# smartStarter.net
KiCad netlist of a schematic drawn in EAGLE
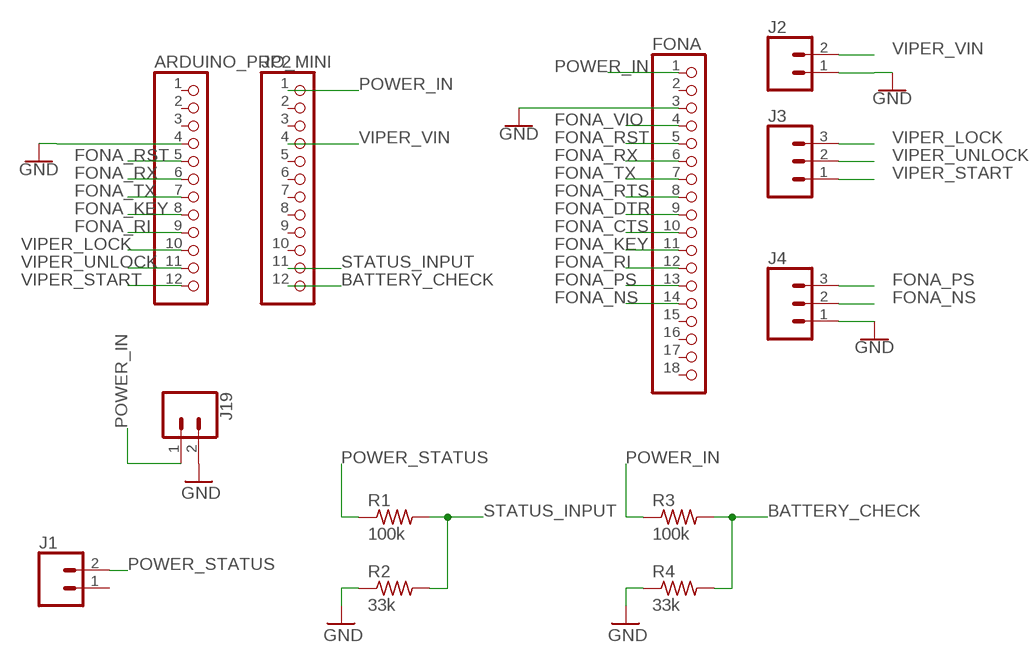
[diagram p0: schematic, sheet 1]

(export (version "E")
  (design (tool "Eeschema 10.0.6"))
  (components
    (comp (ref "ARDUINO_PRO_MINI")
      (value "PINHD-1X12")
      (footprint "eagle-import:1X12")
      (libsource (lib "eagle-import") (part "PINHD-1X12"))
    )
    (comp (ref "FONA")
      (value "PINHD-1X18")
      (footprint "eagle-import:1X18")
      (libsource (lib "eagle-import") (part "PINHD-1X18"))
    )
    (comp (ref "J1")
      (value "CONN_023.5MM")
      (footprint "eagle-import:SCREWTERMINAL-3.5MM-2")
      (libsource (lib "eagle-import") (part "CONN_023.5MM"))
    )
    (comp (ref "J2")
      (value "CONN_023.5MM")
      (footprint "eagle-import:SCREWTERMINAL-3.5MM-2")
      (libsource (lib "eagle-import") (part "CONN_023.5MM"))
    )
    (comp (ref "J3")
      (value "CONN_03SCREW")
      (footprint "eagle-import:SCREWTERMINAL-3.5MM-3")
      (libsource (lib "eagle-import") (part "CONN_03SCREW"))
    )
    (comp (ref "J4")
      (value "CONN_03SCREW")
      (footprint "eagle-import:SCREWTERMINAL-3.5MM-3")
      (libsource (lib "eagle-import") (part "CONN_03SCREW"))
    )
    (comp (ref "J19")
      (value "CONN_023.5MM")
      (footprint "eagle-import:SCREWTERMINAL-3.5MM-2")
      (libsource (lib "eagle-import") (part "CONN_023.5MM"))
    )
    (comp (ref "JP2")
      (value "PINHD-1X12")
      (footprint "eagle-import:1X12")
      (libsource (lib "eagle-import") (part "PINHD-1X12"))
    )
    (comp (ref "R1")
      (value "100k")
      (footprint "eagle-import:0204_7")
      (libsource (lib "eagle-import") (part "R-US_0204/7"))
    )
    (comp (ref "R2")
      (value "33k")
      (footprint "eagle-import:0204_7")
      (libsource (lib "eagle-import") (part "R-US_0204/7"))
    )
    (comp (ref "R3")
      (value "100k")
      (footprint "eagle-import:0204_7")
      (libsource (lib "eagle-import") (part "R-US_0204/7"))
    )
    (comp (ref "R4")
      (value "33k")
      (footprint "eagle-import:0204_7")
      (libsource (lib "eagle-import") (part "R-US_0204/7"))
    )
  )
  (nets
    (net (code "1") (name "/BATTERY_CHECK") (class "Default")
      (node (ref "JP2") (pin "12") (pinfunction "12_12") (pintype "passive"))
      (node (ref "R3") (pin "2") (pinfunction "2_2") (pintype "passive"))
      (node (ref "R4") (pin "2") (pinfunction "2_2") (pintype "passive"))
    )
    (net (code "2") (name "/FONA_CTS") (class "Default")
      (node (ref "FONA") (pin "10") (pinfunction "10_10") (pintype "passive"))
    )
    (net (code "3") (name "/FONA_DTR") (class "Default")
      (node (ref "FONA") (pin "9") (pinfunction "9_9") (pintype "passive"))
    )
    (net (code "4") (name "/FONA_KEY") (class "Default")
      (node (ref "ARDUINO_PRO_MINI") (pin "8") (pinfunction "8_8") (pintype "passive"))
      (node (ref "FONA") (pin "11") (pinfunction "11_11") (pintype "passive"))
    )
    (net (code "5") (name "/FONA_NS") (class "Default")
      (node (ref "FONA") (pin "14") (pinfunction "14_14") (pintype "passive"))
      (node (ref "J4") (pin "2") (pinfunction "2_2") (pintype "passive"))
    )
    (net (code "6") (name "/FONA_PS") (class "Default")
      (node (ref "FONA") (pin "13") (pinfunction "13_13") (pintype "passive"))
      (node (ref "J4") (pin "3") (pinfunction "3_3") (pintype "passive"))
    )
    (net (code "7") (name "/FONA_RI") (class "Default")
      (node (ref "ARDUINO_PRO_MINI") (pin "9") (pinfunction "9_9") (pintype "passive"))
      (node (ref "FONA") (pin "12") (pinfunction "12_12") (pintype "passive"))
    )
    (net (code "8") (name "/FONA_RST") (class "Default")
      (node (ref "ARDUINO_PRO_MINI") (pin "5") (pinfunction "5_5") (pintype "passive"))
      (node (ref "FONA") (pin "5") (pinfunction "5_5") (pintype "passive"))
    )
    (net (code "9") (name "/FONA_RTS") (class "Default")
      (node (ref "FONA") (pin "8") (pinfunction "8_8") (pintype "passive"))
    )
    (net (code "10") (name "/FONA_RX") (class "Default")
      (node (ref "ARDUINO_PRO_MINI") (pin "6") (pinfunction "6_6") (pintype "passive"))
      (node (ref "FONA") (pin "6") (pinfunction "6_6") (pintype "passive"))
    )
    (net (code "11") (name "/FONA_TX") (class "Default")
      (node (ref "ARDUINO_PRO_MINI") (pin "7") (pinfunction "7_7") (pintype "passive"))
      (node (ref "FONA") (pin "7") (pinfunction "7_7") (pintype "passive"))
    )
    (net (code "12") (name "/FONA_VIO") (class "Default")
      (node (ref "FONA") (pin "4") (pinfunction "4_4") (pintype "passive"))
    )
    (net (code "13") (name "/POWER_IN") (class "Default")
      (node (ref "FONA") (pin "1") (pinfunction "1_1") (pintype "passive"))
      (node (ref "J19") (pin "1") (pinfunction "1_1") (pintype "passive"))
      (node (ref "JP2") (pin "1") (pinfunction "1_1") (pintype "passive"))
      (node (ref "R3") (pin "1") (pinfunction "1_1") (pintype "passive"))
    )
    (net (code "14") (name "/POWER_STATUS") (class "Default")
      (node (ref "J1") (pin "2") (pinfunction "2_2") (pintype "passive"))
      (node (ref "R1") (pin "1") (pinfunction "1_1") (pintype "passive"))
    )
    (net (code "15") (name "/STATUS_INPUT") (class "Default")
      (node (ref "JP2") (pin "11") (pinfunction "11_11") (pintype "passive"))
      (node (ref "R1") (pin "2") (pinfunction "2_2") (pintype "passive"))
      (node (ref "R2") (pin "2") (pinfunction "2_2") (pintype "passive"))
    )
    (net (code "16") (name "/VIPER_LOCK") (class "Default")
      (node (ref "ARDUINO_PRO_MINI") (pin "10") (pinfunction "10_10") (pintype "passive"))
      (node (ref "J3") (pin "3") (pinfunction "3_3") (pintype "passive"))
    )
    (net (code "17") (name "/VIPER_START") (class "Default")
      (node (ref "ARDUINO_PRO_MINI") (pin "12") (pinfunction "12_12") (pintype "passive"))
      (node (ref "J3") (pin "1") (pinfunction "1_1") (pintype "passive"))
    )
    (net (code "18") (name "/VIPER_UNLOCK") (class "Default")
      (node (ref "ARDUINO_PRO_MINI") (pin "11") (pinfunction "11_11") (pintype "passive"))
      (node (ref "J3") (pin "2") (pinfunction "2_2") (pintype "passive"))
    )
    (net (code "19") (name "/VIPER_VIN") (class "Default")
      (node (ref "J2") (pin "2") (pinfunction "2_2") (pintype "passive"))
      (node (ref "JP2") (pin "4") (pinfunction "4_4") (pintype "passive"))
    )
    (net (code "20") (name "GND") (class "Default")
      (node (ref "ARDUINO_PRO_MINI") (pin "4") (pinfunction "4_4") (pintype "passive"))
      (node (ref "FONA") (pin "3") (pinfunction "3_3") (pintype "passive"))
      (node (ref "J19") (pin "2") (pinfunction "2_2") (pintype "passive"))
      (node (ref "J2") (pin "1") (pinfunction "1_1") (pintype "passive"))
      (node (ref "J4") (pin "1") (pinfunction "1_1") (pintype "passive"))
      (node (ref "R2") (pin "1") (pinfunction "1_1") (pintype "passive"))
      (node (ref "R4") (pin "1") (pinfunction "1_1") (pintype "passive"))
    )
    (net (code "21") (name "unconnected-(ARDUINO_PRO_MINI-Pad1)") (class "Default")
      (node (ref "ARDUINO_PRO_MINI") (pin "1") (pinfunction "1_1") (pintype "passive"))
    )
    (net (code "22") (name "unconnected-(ARDUINO_PRO_MINI-Pad2)") (class "Default")
      (node (ref "ARDUINO_PRO_MINI") (pin "2") (pinfunction "2_2") (pintype "passive"))
    )
    (net (code "23") (name "unconnected-(ARDUINO_PRO_MINI-Pad3)") (class "Default")
      (node (ref "ARDUINO_PRO_MINI") (pin "3") (pinfunction "3_3") (pintype "passive"))
    )
    (net (code "24") (name "unconnected-(FONA-Pad2)") (class "Default")
      (node (ref "FONA") (pin "2") (pinfunction "2_2") (pintype "passive"))
    )
    (net (code "25") (name "unconnected-(FONA-Pad15)") (class "Default")
      (node (ref "FONA") (pin "15") (pinfunction "15_15") (pintype "passive"))
    )
    (net (code "26") (name "unconnected-(FONA-Pad16)") (class "Default")
      (node (ref "FONA") (pin "16") (pinfunction "16_16") (pintype "passive"))
    )
    (net (code "27") (name "unconnected-(FONA-Pad17)") (class "Default")
      (node (ref "FONA") (pin "17") (pinfunction "17_17") (pintype "passive"))
    )
    (net (code "28") (name "unconnected-(FONA-Pad18)") (class "Default")
      (node (ref "FONA") (pin "18") (pinfunction "18_18") (pintype "passive"))
    )
    (net (code "29") (name "unconnected-(J1-Pad1)") (class "Default")
      (node (ref "J1") (pin "1") (pinfunction "1_1") (pintype "passive"))
    )
    (net (code "30") (name "unconnected-(JP2-Pad2)") (class "Default")
      (node (ref "JP2") (pin "2") (pinfunction "2_2") (pintype "passive"))
    )
    (net (code "31") (name "unconnected-(JP2-Pad3)") (class "Default")
      (node (ref "JP2") (pin "3") (pinfunction "3_3") (pintype "passive"))
    )
    (net (code "32") (name "unconnected-(JP2-Pad5)") (class "Default")
      (node (ref "JP2") (pin "5") (pinfunction "5_5") (pintype "passive"))
    )
    (net (code "33") (name "unconnected-(JP2-Pad6)") (class "Default")
      (node (ref "JP2") (pin "6") (pinfunction "6_6") (pintype "passive"))
    )
    (net (code "34") (name "unconnected-(JP2-Pad7)") (class "Default")
      (node (ref "JP2") (pin "7") (pinfunction "7_7") (pintype "passive"))
    )
    (net (code "35") (name "unconnected-(JP2-Pad8)") (class "Default")
      (node (ref "JP2") (pin "8") (pinfunction "8_8") (pintype "passive"))
    )
    (net (code "36") (name "unconnected-(JP2-Pad9)") (class "Default")
      (node (ref "JP2") (pin "9") (pinfunction "9_9") (pintype "passive"))
    )
    (net (code "37") (name "unconnected-(JP2-Pad10)") (class "Default")
      (node (ref "JP2") (pin "10") (pinfunction "10_10") (pintype "passive"))
    )
  )
)
